# Board_ESP32_n_2Bluepill.net
KiCad netlist of a schematic drawn in EAGLE
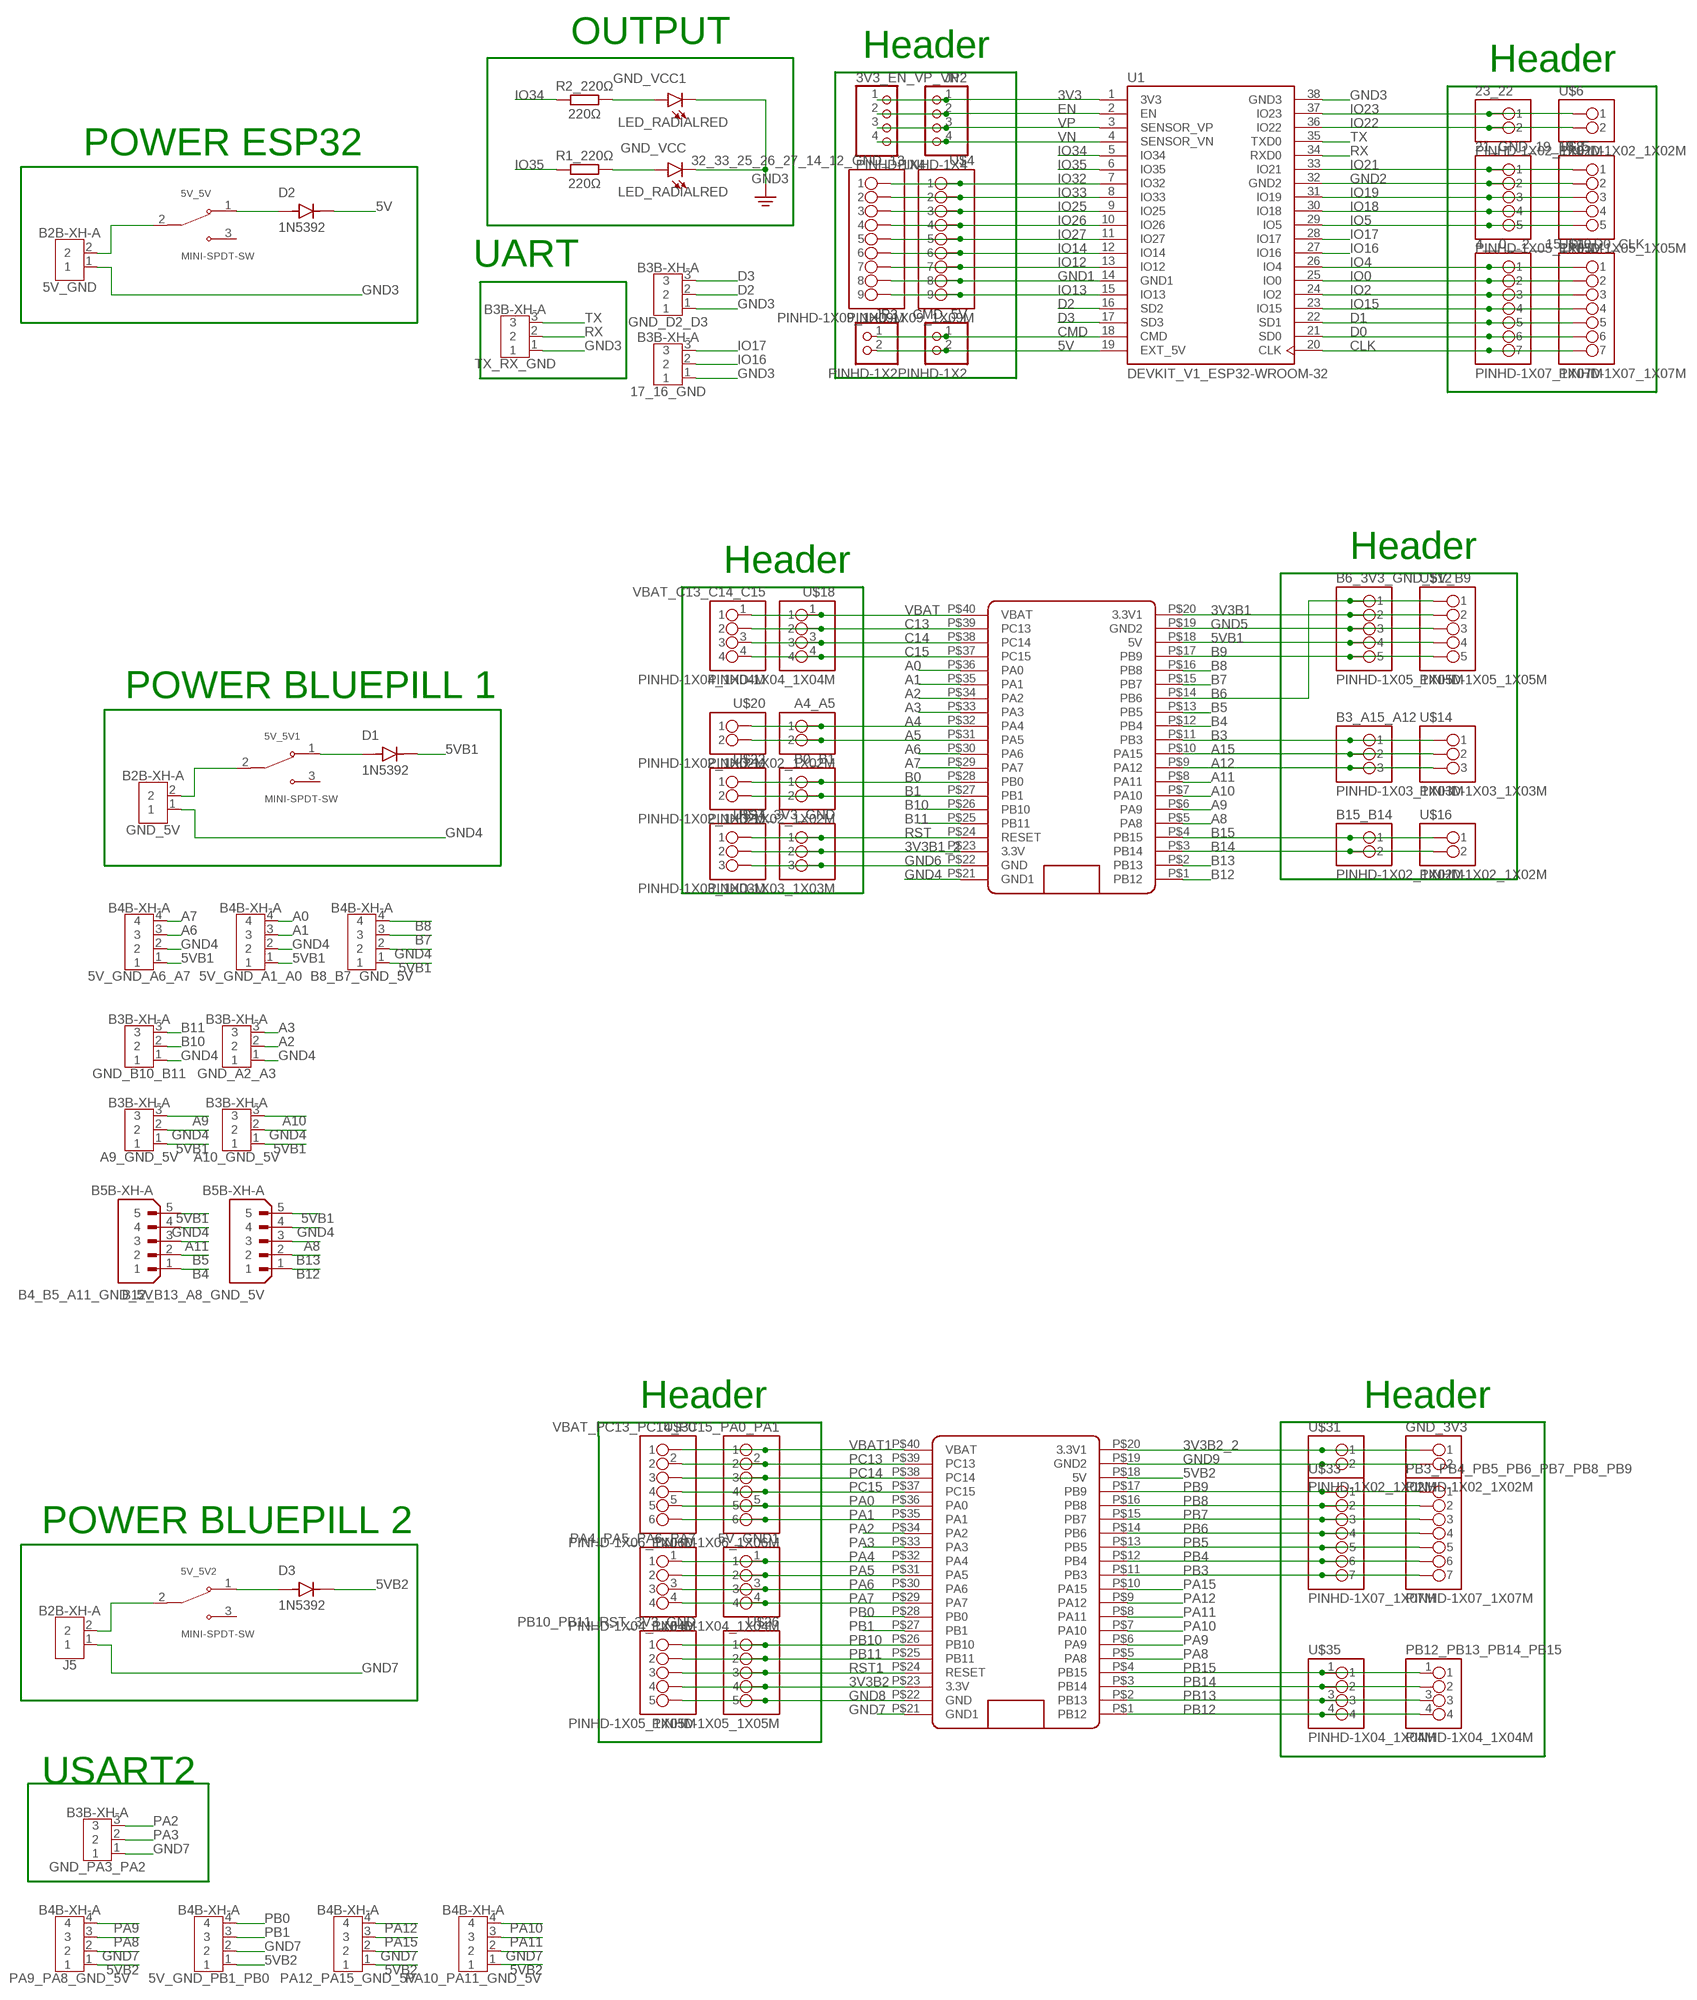
[diagram p0: schematic, sheet 1]

(export (version "E")
  (design (tool "Eeschema 10.0.6"))
  (components
    (comp (ref "3V3_EN_VP_VN")
      (value "PINHD-1X4")
      (footprint "eagle-import:1X04")
      (libsource (lib "eagle-import") (part "PINHD-1X4"))
    )
    (comp (ref "4__0__2__15_D1_D0_CLK")
      (value "PINHD-1X07_1X07M")
      (footprint "eagle-import:1X07")
      (libsource (lib "eagle-import") (part "PINHD-1X07_1X07M"))
    )
    (comp (ref "5V_5V")
      (value "MINI-SPDT-SW")
      (footprint "eagle-import:SW_MINI-SPDT-SW")
      (fields (field (name "MF") "Gravitech"))
      (libsource (lib "eagle-import") (part "MINI-SPDT-SW"))
    )
    (comp (ref "5V_5V1")
      (value "MINI-SPDT-SW")
      (footprint "eagle-import:SW_MINI-SPDT-SW")
      (fields (field (name "MF") "Gravitech"))
      (libsource (lib "eagle-import") (part "MINI-SPDT-SW"))
    )
    (comp (ref "5V_5V2")
      (value "MINI-SPDT-SW")
      (footprint "eagle-import:SW_MINI-SPDT-SW")
      (fields (field (name "MF") "Gravitech"))
      (libsource (lib "eagle-import") (part "MINI-SPDT-SW"))
    )
    (comp (ref "5V_GND")
      (value "B2B-XH-A")
      (footprint "eagle-import:B2B-XH-A")
      (fields (field (name "MANUFACTURER") "JST Sales America Inc."))
      (libsource (lib "eagle-import") (part "B2B-XH-A"))
    )
    (comp (ref "5V_GND1")
      (value "PINHD-1X04_1X04M")
      (footprint "eagle-import:1X04")
      (libsource (lib "eagle-import") (part "PINHD-1X04_1X04M"))
    )
    (comp (ref "5V_GND_A1_A0")
      (value "B4B-XH-A")
      (footprint "eagle-import:B4B-XH-A")
      (fields (field (name "MANUFACTURER") "JST Sales America Inc."))
      (libsource (lib "eagle-import") (part "B4B-XH-A"))
    )
    (comp (ref "5V_GND_A6_A7")
      (value "B4B-XH-A")
      (footprint "eagle-import:B4B-XH-A")
      (fields (field (name "MANUFACTURER") "JST Sales America Inc."))
      (libsource (lib "eagle-import") (part "B4B-XH-A"))
    )
    (comp (ref "5V_GND_PB1_PB0")
      (value "B4B-XH-A")
      (footprint "eagle-import:B4B-XH-A")
      (fields (field (name "MANUFACTURER") "JST Sales America Inc."))
      (libsource (lib "eagle-import") (part "B4B-XH-A"))
    )
    (comp (ref "17_16_GND")
      (value "B3B-XH-A")
      (footprint "eagle-import:B3B-XH-A")
      (fields (field (name "MANUFACTURER") "JST Sales America Inc."))
      (libsource (lib "eagle-import") (part "B3B-XH-A"))
    )
    (comp (ref "21_GND_19_18_5")
      (value "PINHD-1X05_1X05M")
      (footprint "eagle-import:1X05")
      (libsource (lib "eagle-import") (part "PINHD-1X05_1X05M"))
    )
    (comp (ref "23_22")
      (value "PINHD-1X02_1X02M")
      (footprint "eagle-import:1X02")
      (libsource (lib "eagle-import") (part "PINHD-1X02_1X02M"))
    )
    (comp (ref "32_33_25_26_27_14_12_GND_13")
      (value "PINHD-1X09_1X09M")
      (footprint "eagle-import:1X09")
      (libsource (lib "eagle-import") (part "PINHD-1X09_1X09M"))
    )
    (comp (ref "A4_A5")
      (value "PINHD-1X02_1X02M")
      (footprint "eagle-import:1X02")
      (libsource (lib "eagle-import") (part "PINHD-1X02_1X02M"))
    )
    (comp (ref "A9_GND_5V")
      (value "B3B-XH-A")
      (footprint "eagle-import:B3B-XH-A")
      (fields (field (name "MANUFACTURER") "JST Sales America Inc."))
      (libsource (lib "eagle-import") (part "B3B-XH-A"))
    )
    (comp (ref "A10_GND_5V")
      (value "B3B-XH-A")
      (footprint "eagle-import:B3B-XH-A")
      (fields (field (name "MANUFACTURER") "JST Sales America Inc."))
      (libsource (lib "eagle-import") (part "B3B-XH-A"))
    )
    (comp (ref "B0_B1")
      (value "PINHD-1X02_1X02M")
      (footprint "eagle-import:1X02")
      (libsource (lib "eagle-import") (part "PINHD-1X02_1X02M"))
    )
    (comp (ref "B3_A15_A12")
      (value "PINHD-1X03_1X03M")
      (footprint "eagle-import:1X03")
      (libsource (lib "eagle-import") (part "PINHD-1X03_1X03M"))
    )
    (comp (ref "B4_B5_A11_GND_5V")
      (value "B5B-XH-A")
      (footprint "eagle-import:JST_B5B-XH-A")
      (fields (field (name "MF") "JST Sales"))
      (libsource (lib "eagle-import") (part "B5B-XH-A"))
    )
    (comp (ref "B6_3V3_GND_5V_B9")
      (value "PINHD-1X05_1X05M")
      (footprint "eagle-import:1X05")
      (libsource (lib "eagle-import") (part "PINHD-1X05_1X05M"))
    )
    (comp (ref "B8_B7_GND_5V")
      (value "B4B-XH-A")
      (footprint "eagle-import:B4B-XH-A")
      (fields (field (name "MANUFACTURER") "JST Sales America Inc."))
      (libsource (lib "eagle-import") (part "B4B-XH-A"))
    )
    (comp (ref "B12_B13_A8_GND_5V")
      (value "B5B-XH-A")
      (footprint "eagle-import:JST_B5B-XH-A")
      (fields (field (name "MF") "JST Sales"))
      (libsource (lib "eagle-import") (part "B5B-XH-A"))
    )
    (comp (ref "B15_B14")
      (value "PINHD-1X02_1X02M")
      (footprint "eagle-import:1X02")
      (libsource (lib "eagle-import") (part "PINHD-1X02_1X02M"))
    )
    (comp (ref "CMD_5V")
      (value "PINHD-1X2")
      (footprint "eagle-import:1X02")
      (libsource (lib "eagle-import") (part "PINHD-1X2"))
    )
    (comp (ref "D1")
      (value "1N5392")
      (footprint "eagle-import:DIOAD1300W80L670D310")
      (fields (field (name "MF") "ON Semiconductor"))
      (libsource (lib "eagle-import") (part "1N5392"))
    )
    (comp (ref "D2")
      (value "1N5392")
      (footprint "eagle-import:DIOAD1300W80L670D310")
      (fields (field (name "MF") "ON Semiconductor"))
      (libsource (lib "eagle-import") (part "1N5392"))
    )
    (comp (ref "D3")
      (value "1N5392")
      (footprint "eagle-import:DIOAD1300W80L670D310")
      (fields (field (name "MF") "ON Semiconductor"))
      (libsource (lib "eagle-import") (part "1N5392"))
    )
    (comp (ref "GND_3V3")
      (value "PINHD-1X02_1X02M")
      (footprint "eagle-import:1X02")
      (libsource (lib "eagle-import") (part "PINHD-1X02_1X02M"))
    )
    (comp (ref "GND_5V")
      (value "B2B-XH-A")
      (footprint "eagle-import:B2B-XH-A")
      (fields (field (name "MANUFACTURER") "JST Sales America Inc."))
      (libsource (lib "eagle-import") (part "B2B-XH-A"))
    )
    (comp (ref "GND_A2_A3")
      (value "B3B-XH-A")
      (footprint "eagle-import:B3B-XH-A")
      (fields (field (name "MANUFACTURER") "JST Sales America Inc."))
      (libsource (lib "eagle-import") (part "B3B-XH-A"))
    )
    (comp (ref "GND_B10_B11")
      (value "B3B-XH-A")
      (footprint "eagle-import:B3B-XH-A")
      (fields (field (name "MANUFACTURER") "JST Sales America Inc."))
      (libsource (lib "eagle-import") (part "B3B-XH-A"))
    )
    (comp (ref "GND_D2_D3")
      (value "B3B-XH-A")
      (footprint "eagle-import:B3B-XH-A")
      (fields (field (name "MANUFACTURER") "JST Sales America Inc."))
      (libsource (lib "eagle-import") (part "B3B-XH-A"))
    )
    (comp (ref "GND_PA3_PA2")
      (value "B3B-XH-A")
      (footprint "eagle-import:B3B-XH-A")
      (fields (field (name "MANUFACTURER") "JST Sales America Inc."))
      (libsource (lib "eagle-import") (part "B3B-XH-A"))
    )
    (comp (ref "GND_VCC")
      (value "LED_RADIALRED")
      (footprint "eagle-import:LEDRD254W60D565H860B_R")
      (libsource (lib "eagle-import") (part "LED_RADIALRED"))
    )
    (comp (ref "GND_VCC1")
      (value "LED_RADIALRED")
      (footprint "eagle-import:LEDRD254W60D565H860B_R")
      (libsource (lib "eagle-import") (part "LED_RADIALRED"))
    )
    (comp (ref "J5")
      (value "B2B-XH-A")
      (footprint "eagle-import:B2B-XH-A")
      (fields (field (name "MANUFACTURER") "JST Sales America Inc."))
      (libsource (lib "eagle-import") (part "B2B-XH-A"))
    )
    (comp (ref "JP2")
      (value "PINHD-1X4")
      (footprint "eagle-import:1X04")
      (libsource (lib "eagle-import") (part "PINHD-1X4"))
    )
    (comp (ref "JP3")
      (value "PINHD-1X2")
      (footprint "eagle-import:1X02")
      (libsource (lib "eagle-import") (part "PINHD-1X2"))
    )
    (comp (ref "PA4_PA5_PA6_PA7")
      (value "PINHD-1X04_1X04M")
      (footprint "eagle-import:1X04")
      (libsource (lib "eagle-import") (part "PINHD-1X04_1X04M"))
    )
    (comp (ref "PA9_PA8_GND_5V")
      (value "B4B-XH-A")
      (footprint "eagle-import:B4B-XH-A")
      (fields (field (name "MANUFACTURER") "JST Sales America Inc."))
      (libsource (lib "eagle-import") (part "B4B-XH-A"))
    )
    (comp (ref "PA10_PA11_GND_5V")
      (value "B4B-XH-A")
      (footprint "eagle-import:B4B-XH-A")
      (fields (field (name "MANUFACTURER") "JST Sales America Inc."))
      (libsource (lib "eagle-import") (part "B4B-XH-A"))
    )
    (comp (ref "PA12_PA15_GND_5V")
      (value "B4B-XH-A")
      (footprint "eagle-import:B4B-XH-A")
      (fields (field (name "MANUFACTURER") "JST Sales America Inc."))
      (libsource (lib "eagle-import") (part "B4B-XH-A"))
    )
    (comp (ref "PB3_PB4_PB5_PB6_PB7_PB8_PB9")
      (value "PINHD-1X07_1X07M")
      (footprint "eagle-import:1X07")
      (libsource (lib "eagle-import") (part "PINHD-1X07_1X07M"))
    )
    (comp (ref "PB10_PB11_RST_3V3_GND")
      (value "PINHD-1X05_1X05M")
      (footprint "eagle-import:1X05")
      (libsource (lib "eagle-import") (part "PINHD-1X05_1X05M"))
    )
    (comp (ref "PB12_PB13_PB14_PB15")
      (value "PINHD-1X04_1X04M")
      (footprint "eagle-import:1X04")
      (libsource (lib "eagle-import") (part "PINHD-1X04_1X04M"))
    )
    (comp (ref "R1_220Ω")
      (value "220Ω")
      (footprint "eagle-import:RESAD1176W63L850D250B")
      (libsource (lib "eagle-import") (part "RAXIAL-11.7MM-PITCH_"))
    )
    (comp (ref "R2_220Ω")
      (value "220Ω")
      (footprint "eagle-import:RESAD1176W63L850D250B")
      (libsource (lib "eagle-import") (part "RAXIAL-11.7MM-PITCH_"))
    )
    (comp (ref "RST_3V3_GND")
      (value "PINHD-1X03_1X03M")
      (footprint "eagle-import:1X03")
      (libsource (lib "eagle-import") (part "PINHD-1X03_1X03M"))
    )
    (comp (ref "TX_RX_GND")
      (value "B3B-XH-A")
      (footprint "eagle-import:B3B-XH-A")
      (fields (field (name "MANUFACTURER") "JST Sales America Inc."))
      (libsource (lib "eagle-import") (part "B3B-XH-A"))
    )
    (comp (ref "U$1")
      (value "BLUE_PILL")
      (footprint "eagle-import:BLUE_PILL")
      (libsource (lib "eagle-import") (part "BLUE_PILL"))
    )
    (comp (ref "U$2")
      (value "BLUE_PILL")
      (footprint "eagle-import:BLUE_PILL")
      (libsource (lib "eagle-import") (part "BLUE_PILL"))
    )
    (comp (ref "U$4")
      (value "PINHD-1X09_1X09M")
      (footprint "eagle-import:1X09")
      (libsource (lib "eagle-import") (part "PINHD-1X09_1X09M"))
    )
    (comp (ref "U$6")
      (value "PINHD-1X02_1X02M")
      (footprint "eagle-import:1X02")
      (libsource (lib "eagle-import") (part "PINHD-1X02_1X02M"))
    )
    (comp (ref "U$8")
      (value "PINHD-1X05_1X05M")
      (footprint "eagle-import:1X05")
      (libsource (lib "eagle-import") (part "PINHD-1X05_1X05M"))
    )
    (comp (ref "U$10")
      (value "PINHD-1X07_1X07M")
      (footprint "eagle-import:1X07")
      (libsource (lib "eagle-import") (part "PINHD-1X07_1X07M"))
    )
    (comp (ref "U$12")
      (value "PINHD-1X05_1X05M")
      (footprint "eagle-import:1X05")
      (libsource (lib "eagle-import") (part "PINHD-1X05_1X05M"))
    )
    (comp (ref "U$14")
      (value "PINHD-1X03_1X03M")
      (footprint "eagle-import:1X03")
      (libsource (lib "eagle-import") (part "PINHD-1X03_1X03M"))
    )
    (comp (ref "U$16")
      (value "PINHD-1X02_1X02M")
      (footprint "eagle-import:1X02")
      (libsource (lib "eagle-import") (part "PINHD-1X02_1X02M"))
    )
    (comp (ref "U$18")
      (value "PINHD-1X04_1X04M")
      (footprint "eagle-import:1X04")
      (libsource (lib "eagle-import") (part "PINHD-1X04_1X04M"))
    )
    (comp (ref "U$20")
      (value "PINHD-1X02_1X02M")
      (footprint "eagle-import:1X02")
      (libsource (lib "eagle-import") (part "PINHD-1X02_1X02M"))
    )
    (comp (ref "U$22")
      (value "PINHD-1X02_1X02M")
      (footprint "eagle-import:1X02")
      (libsource (lib "eagle-import") (part "PINHD-1X02_1X02M"))
    )
    (comp (ref "U$24")
      (value "PINHD-1X03_1X03M")
      (footprint "eagle-import:1X03")
      (libsource (lib "eagle-import") (part "PINHD-1X03_1X03M"))
    )
    (comp (ref "U$26")
      (value "PINHD-1X05_1X05M")
      (footprint "eagle-import:1X05")
      (libsource (lib "eagle-import") (part "PINHD-1X05_1X05M"))
    )
    (comp (ref "U$30")
      (value "PINHD-1X06_1X06M")
      (footprint "eagle-import:1X06")
      (libsource (lib "eagle-import") (part "PINHD-1X06_1X06M"))
    )
    (comp (ref "U$31")
      (value "PINHD-1X02_1X02M")
      (footprint "eagle-import:1X02")
      (libsource (lib "eagle-import") (part "PINHD-1X02_1X02M"))
    )
    (comp (ref "U$33")
      (value "PINHD-1X07_1X07M")
      (footprint "eagle-import:1X07")
      (libsource (lib "eagle-import") (part "PINHD-1X07_1X07M"))
    )
    (comp (ref "U$35")
      (value "PINHD-1X04_1X04M")
      (footprint "eagle-import:1X04")
      (libsource (lib "eagle-import") (part "PINHD-1X04_1X04M"))
    )
    (comp (ref "U1")
      (value "DEVKIT_V1_ESP32-WROOM-32")
      (footprint "eagle-import:MODULE_DEVKIT_V1_ESP32-WROOM-32")
      (fields (field (name "MF") "Espressif Systems") (field (name "MP") "DEVKIT V1 ESP32-WROOM-32"))
      (libsource (lib "eagle-import") (part "DEVKIT_V1_ESP32-WROOM-32"))
    )
    (comp (ref "VBAT_C13_C14_C15")
      (value "PINHD-1X04_1X04M")
      (footprint "eagle-import:1X04")
      (libsource (lib "eagle-import") (part "PINHD-1X04_1X04M"))
    )
    (comp (ref "VBAT_PC13_PC14_PC15_PA0_PA1")
      (value "PINHD-1X06_1X06M")
      (footprint "eagle-import:1X06")
      (libsource (lib "eagle-import") (part "PINHD-1X06_1X06M"))
    )
  )
  (nets
    (net (code "1") (name "/3V3") (class "Default")
      (node (ref "3V3_EN_VP_VN") (pin "1") (pinfunction "1_1") (pintype "passive"))
      (node (ref "JP2") (pin "1") (pinfunction "1_1") (pintype "passive"))
      (node (ref "U1") (pin "1") (pinfunction "3V3_1") (pintype "power_in"))
    )
    (net (code "2") (name "/3V3B1") (class "Default")
      (node (ref "B6_3V3_GND_5V_B9") (pin "2") (pinfunction "2_2") (pintype "bidirectional"))
      (node (ref "U$1") (pin "P$20") (pinfunction "3.3V1_P$20") (pintype "bidirectional"))
      (node (ref "U$12") (pin "2") (pinfunction "2_2") (pintype "bidirectional"))
    )
    (net (code "3") (name "/3V3B1_2") (class "Default")
      (node (ref "RST_3V3_GND") (pin "2") (pinfunction "2_2") (pintype "bidirectional"))
      (node (ref "U$1") (pin "P$23") (pinfunction "3.3V_P$23") (pintype "bidirectional"))
      (node (ref "U$24") (pin "2") (pinfunction "2_2") (pintype "bidirectional"))
    )
    (net (code "4") (name "/3V3B2") (class "Default")
      (node (ref "PB10_PB11_RST_3V3_GND") (pin "4") (pinfunction "4_4") (pintype "bidirectional"))
      (node (ref "U$2") (pin "P$23") (pinfunction "3.3V_P$23") (pintype "bidirectional"))
      (node (ref "U$26") (pin "4") (pinfunction "4_4") (pintype "bidirectional"))
    )
    (net (code "5") (name "/3V3B2_2") (class "Default")
      (node (ref "GND_3V3") (pin "1") (pinfunction "1_1") (pintype "bidirectional"))
      (node (ref "U$2") (pin "P$20") (pinfunction "3.3V1_P$20") (pintype "bidirectional"))
      (node (ref "U$31") (pin "1") (pinfunction "1_1") (pintype "bidirectional"))
    )
    (net (code "6") (name "/5V") (class "Default")
      (node (ref "CMD_5V") (pin "2") (pinfunction "2_2") (pintype "passive"))
      (node (ref "D2") (pin "C") (pinfunction "K_C") (pintype "passive"))
      (node (ref "JP3") (pin "2") (pinfunction "2_2") (pintype "passive"))
      (node (ref "U1") (pin "19") (pinfunction "EXT_5V_19") (pintype "power_in"))
    )
    (net (code "7") (name "/5VB1") (class "Default")
      (node (ref "5V_GND_A1_A0") (pin "1") (pinfunction "1_1") (pintype "bidirectional"))
      (node (ref "5V_GND_A6_A7") (pin "1") (pinfunction "1_1") (pintype "bidirectional"))
      (node (ref "A10_GND_5V") (pin "1") (pinfunction "1_1") (pintype "bidirectional"))
      (node (ref "A9_GND_5V") (pin "1") (pinfunction "1_1") (pintype "bidirectional"))
      (node (ref "B12_B13_A8_GND_5V") (pin "5") (pinfunction "5_5") (pintype "passive"))
      (node (ref "B4_B5_A11_GND_5V") (pin "5") (pinfunction "5_5") (pintype "passive"))
      (node (ref "B6_3V3_GND_5V_B9") (pin "4") (pinfunction "4_4") (pintype "bidirectional"))
      (node (ref "B8_B7_GND_5V") (pin "1") (pinfunction "1_1") (pintype "bidirectional"))
      (node (ref "D1") (pin "C") (pinfunction "K_C") (pintype "passive"))
      (node (ref "U$1") (pin "P$18") (pinfunction "5V_P$18") (pintype "bidirectional"))
      (node (ref "U$12") (pin "4") (pinfunction "4_4") (pintype "bidirectional"))
    )
    (net (code "8") (name "/5VB2") (class "Default")
      (node (ref "5V_GND_PB1_PB0") (pin "1") (pinfunction "1_1") (pintype "bidirectional"))
      (node (ref "D3") (pin "C") (pinfunction "K_C") (pintype "passive"))
      (node (ref "PA10_PA11_GND_5V") (pin "1") (pinfunction "1_1") (pintype "bidirectional"))
      (node (ref "PA12_PA15_GND_5V") (pin "1") (pinfunction "1_1") (pintype "bidirectional"))
      (node (ref "PA9_PA8_GND_5V") (pin "1") (pinfunction "1_1") (pintype "bidirectional"))
      (node (ref "U$2") (pin "P$18") (pinfunction "5V_P$18") (pintype "bidirectional"))
    )
    (net (code "9") (name "/A0") (class "Default")
      (node (ref "5V_GND_A1_A0") (pin "4") (pinfunction "4_4") (pintype "bidirectional"))
      (node (ref "U$1") (pin "P$36") (pinfunction "PA0_P$36") (pintype "bidirectional"))
    )
    (net (code "10") (name "/A1") (class "Default")
      (node (ref "5V_GND_A1_A0") (pin "3") (pinfunction "3_3") (pintype "bidirectional"))
      (node (ref "U$1") (pin "P$35") (pinfunction "PA1_P$35") (pintype "bidirectional"))
    )
    (net (code "11") (name "/A2") (class "Default")
      (node (ref "GND_A2_A3") (pin "2") (pinfunction "2_2") (pintype "bidirectional"))
      (node (ref "U$1") (pin "P$34") (pinfunction "PA2_P$34") (pintype "bidirectional"))
    )
    (net (code "12") (name "/A3") (class "Default")
      (node (ref "GND_A2_A3") (pin "3") (pinfunction "3_3") (pintype "bidirectional"))
      (node (ref "U$1") (pin "P$33") (pinfunction "PA3_P$33") (pintype "bidirectional"))
    )
    (net (code "13") (name "/A4") (class "Default")
      (node (ref "A4_A5") (pin "1") (pinfunction "1_1") (pintype "bidirectional"))
      (node (ref "U$1") (pin "P$32") (pinfunction "PA4_P$32") (pintype "bidirectional"))
      (node (ref "U$20") (pin "1") (pinfunction "1_1") (pintype "bidirectional"))
    )
    (net (code "14") (name "/A5") (class "Default")
      (node (ref "A4_A5") (pin "2") (pinfunction "2_2") (pintype "bidirectional"))
      (node (ref "U$1") (pin "P$31") (pinfunction "PA5_P$31") (pintype "bidirectional"))
      (node (ref "U$20") (pin "2") (pinfunction "2_2") (pintype "bidirectional"))
    )
    (net (code "15") (name "/A6") (class "Default")
      (node (ref "5V_GND_A6_A7") (pin "3") (pinfunction "3_3") (pintype "bidirectional"))
      (node (ref "U$1") (pin "P$30") (pinfunction "PA6_P$30") (pintype "bidirectional"))
    )
    (net (code "16") (name "/A7") (class "Default")
      (node (ref "5V_GND_A6_A7") (pin "4") (pinfunction "4_4") (pintype "bidirectional"))
      (node (ref "U$1") (pin "P$29") (pinfunction "PA7_P$29") (pintype "bidirectional"))
    )
    (net (code "17") (name "/A8") (class "Default")
      (node (ref "B12_B13_A8_GND_5V") (pin "3") (pinfunction "3_3") (pintype "passive"))
      (node (ref "U$1") (pin "P$5") (pinfunction "PA8_P$5") (pintype "bidirectional"))
    )
    (net (code "18") (name "/A9") (class "Default")
      (node (ref "A9_GND_5V") (pin "3") (pinfunction "3_3") (pintype "bidirectional"))
      (node (ref "U$1") (pin "P$6") (pinfunction "PA9_P$6") (pintype "bidirectional"))
    )
    (net (code "19") (name "/A10") (class "Default")
      (node (ref "A10_GND_5V") (pin "3") (pinfunction "3_3") (pintype "bidirectional"))
      (node (ref "U$1") (pin "P$7") (pinfunction "PA10_P$7") (pintype "bidirectional"))
    )
    (net (code "20") (name "/A11") (class "Default")
      (node (ref "B4_B5_A11_GND_5V") (pin "3") (pinfunction "3_3") (pintype "passive"))
      (node (ref "U$1") (pin "P$8") (pinfunction "PA11_P$8") (pintype "bidirectional"))
    )
    (net (code "21") (name "/A12") (class "Default")
      (node (ref "B3_A15_A12") (pin "3") (pinfunction "3_3") (pintype "bidirectional"))
      (node (ref "U$1") (pin "P$9") (pinfunction "PA12_P$9") (pintype "bidirectional"))
      (node (ref "U$14") (pin "3") (pinfunction "3_3") (pintype "bidirectional"))
    )
    (net (code "22") (name "/A15") (class "Default")
      (node (ref "B3_A15_A12") (pin "2") (pinfunction "2_2") (pintype "bidirectional"))
      (node (ref "U$1") (pin "P$10") (pinfunction "PA15_P$10") (pintype "bidirectional"))
      (node (ref "U$14") (pin "2") (pinfunction "2_2") (pintype "bidirectional"))
    )
    (net (code "23") (name "/B0") (class "Default")
      (node (ref "B0_B1") (pin "1") (pinfunction "1_1") (pintype "bidirectional"))
      (node (ref "U$1") (pin "P$28") (pinfunction "PB0_P$28") (pintype "bidirectional"))
      (node (ref "U$22") (pin "1") (pinfunction "1_1") (pintype "bidirectional"))
    )
    (net (code "24") (name "/B1") (class "Default")
      (node (ref "B0_B1") (pin "2") (pinfunction "2_2") (pintype "bidirectional"))
      (node (ref "U$1") (pin "P$27") (pinfunction "PB1_P$27") (pintype "bidirectional"))
      (node (ref "U$22") (pin "2") (pinfunction "2_2") (pintype "bidirectional"))
    )
    (net (code "25") (name "/B3") (class "Default")
      (node (ref "B3_A15_A12") (pin "1") (pinfunction "1_1") (pintype "bidirectional"))
      (node (ref "U$1") (pin "P$11") (pinfunction "PB3_P$11") (pintype "bidirectional"))
      (node (ref "U$14") (pin "1") (pinfunction "1_1") (pintype "bidirectional"))
    )
    (net (code "26") (name "/B4") (class "Default")
      (node (ref "B4_B5_A11_GND_5V") (pin "1") (pinfunction "1_1") (pintype "passive"))
      (node (ref "U$1") (pin "P$12") (pinfunction "PB4_P$12") (pintype "bidirectional"))
    )
    (net (code "27") (name "/B5") (class "Default")
      (node (ref "B4_B5_A11_GND_5V") (pin "2") (pinfunction "2_2") (pintype "passive"))
      (node (ref "U$1") (pin "P$13") (pinfunction "PB5_P$13") (pintype "bidirectional"))
    )
    (net (code "28") (name "/B6") (class "Default")
      (node (ref "B6_3V3_GND_5V_B9") (pin "1") (pinfunction "1_1") (pintype "bidirectional"))
      (node (ref "U$1") (pin "P$14") (pinfunction "PB6_P$14") (pintype "bidirectional"))
      (node (ref "U$12") (pin "1") (pinfunction "1_1") (pintype "bidirectional"))
    )
    (net (code "29") (name "/B7") (class "Default")
      (node (ref "B8_B7_GND_5V") (pin "3") (pinfunction "3_3") (pintype "bidirectional"))
      (node (ref "U$1") (pin "P$15") (pinfunction "PB7_P$15") (pintype "bidirectional"))
    )
    (net (code "30") (name "/B8") (class "Default")
      (node (ref "B8_B7_GND_5V") (pin "4") (pinfunction "4_4") (pintype "bidirectional"))
      (node (ref "U$1") (pin "P$16") (pinfunction "PB8_P$16") (pintype "bidirectional"))
    )
    (net (code "31") (name "/B9") (class "Default")
      (node (ref "B6_3V3_GND_5V_B9") (pin "5") (pinfunction "5_5") (pintype "bidirectional"))
      (node (ref "U$1") (pin "P$17") (pinfunction "PB9_P$17") (pintype "bidirectional"))
      (node (ref "U$12") (pin "5") (pinfunction "5_5") (pintype "bidirectional"))
    )
    (net (code "32") (name "/B10") (class "Default")
      (node (ref "GND_B10_B11") (pin "2") (pinfunction "2_2") (pintype "bidirectional"))
      (node (ref "U$1") (pin "P$26") (pinfunction "PB10_P$26") (pintype "bidirectional"))
    )
    (net (code "33") (name "/B11") (class "Default")
      (node (ref "GND_B10_B11") (pin "3") (pinfunction "3_3") (pintype "bidirectional"))
      (node (ref "U$1") (pin "P$25") (pinfunction "PB11_P$25") (pintype "bidirectional"))
    )
    (net (code "34") (name "/B12") (class "Default")
      (node (ref "B12_B13_A8_GND_5V") (pin "1") (pinfunction "1_1") (pintype "passive"))
      (node (ref "U$1") (pin "P$1") (pinfunction "PB12_P$1") (pintype "bidirectional"))
    )
    (net (code "35") (name "/B13") (class "Default")
      (node (ref "B12_B13_A8_GND_5V") (pin "2") (pinfunction "2_2") (pintype "passive"))
      (node (ref "U$1") (pin "P$2") (pinfunction "PB13_P$2") (pintype "bidirectional"))
    )
    (net (code "36") (name "/B14") (class "Default")
      (node (ref "B15_B14") (pin "2") (pinfunction "2_2") (pintype "bidirectional"))
      (node (ref "U$1") (pin "P$3") (pinfunction "PB14_P$3") (pintype "bidirectional"))
      (node (ref "U$16") (pin "2") (pinfunction "2_2") (pintype "bidirectional"))
    )
    (net (code "37") (name "/B15") (class "Default")
      (node (ref "B15_B14") (pin "1") (pinfunction "1_1") (pintype "bidirectional"))
      (node (ref "U$1") (pin "P$4") (pinfunction "PB15_P$4") (pintype "bidirectional"))
      (node (ref "U$16") (pin "1") (pinfunction "1_1") (pintype "bidirectional"))
    )
    (net (code "38") (name "/C13") (class "Default")
      (node (ref "U$1") (pin "P$39") (pinfunction "PC13_P$39") (pintype "bidirectional"))
      (node (ref "U$18") (pin "2") (pinfunction "2_2") (pintype "bidirectional"))
      (node (ref "VBAT_C13_C14_C15") (pin "2") (pinfunction "2_2") (pintype "bidirectional"))
    )
    (net (code "39") (name "/C14") (class "Default")
      (node (ref "U$1") (pin "P$38") (pinfunction "PC14_P$38") (pintype "bidirectional"))
      (node (ref "U$18") (pin "3") (pinfunction "3_3") (pintype "bidirectional"))
      (node (ref "VBAT_C13_C14_C15") (pin "3") (pinfunction "3_3") (pintype "bidirectional"))
    )
    (net (code "40") (name "/C15") (class "Default")
      (node (ref "U$1") (pin "P$37") (pinfunction "PC15_P$37") (pintype "bidirectional"))
      (node (ref "U$18") (pin "4") (pinfunction "4_4") (pintype "bidirectional"))
      (node (ref "VBAT_C13_C14_C15") (pin "4") (pinfunction "4_4") (pintype "bidirectional"))
    )
    (net (code "41") (name "/CLK") (class "Default")
      (node (ref "4__0__2__15_D1_D0_CLK") (pin "7") (pinfunction "7_7") (pintype "bidirectional"))
      (node (ref "U$10") (pin "7") (pinfunction "7_7") (pintype "bidirectional"))
      (node (ref "U1") (pin "20") (pinfunction "CLK_20") (pintype "input"))
    )
    (net (code "42") (name "/CMD") (class "Default")
      (node (ref "CMD_5V") (pin "1") (pinfunction "1_1") (pintype "passive"))
      (node (ref "JP3") (pin "1") (pinfunction "1_1") (pintype "passive"))
      (node (ref "U1") (pin "18") (pinfunction "CMD_18") (pintype "bidirectional"))
    )
    (net (code "43") (name "/D0") (class "Default")
      (node (ref "4__0__2__15_D1_D0_CLK") (pin "6") (pinfunction "6_6") (pintype "bidirectional"))
      (node (ref "U$10") (pin "6") (pinfunction "6_6") (pintype "bidirectional"))
      (node (ref "U1") (pin "21") (pinfunction "SD0_21") (pintype "bidirectional"))
    )
    (net (code "44") (name "/D1") (class "Default")
      (node (ref "4__0__2__15_D1_D0_CLK") (pin "5") (pinfunction "5_5") (pintype "bidirectional"))
      (node (ref "U$10") (pin "5") (pinfunction "5_5") (pintype "bidirectional"))
      (node (ref "U1") (pin "22") (pinfunction "SD1_22") (pintype "bidirectional"))
    )
    (net (code "45") (name "/D2") (class "Default")
      (node (ref "GND_D2_D3") (pin "2") (pinfunction "2_2") (pintype "bidirectional"))
      (node (ref "U1") (pin "16") (pinfunction "SD2_16") (pintype "bidirectional"))
    )
    (net (code "46") (name "/D3") (class "Default")
      (node (ref "GND_D2_D3") (pin "3") (pinfunction "3_3") (pintype "bidirectional"))
      (node (ref "U1") (pin "17") (pinfunction "SD3_17") (pintype "bidirectional"))
    )
    (net (code "47") (name "/EN") (class "Default")
      (node (ref "3V3_EN_VP_VN") (pin "2") (pinfunction "2_2") (pintype "passive"))
      (node (ref "JP2") (pin "2") (pinfunction "2_2") (pintype "passive"))
      (node (ref "U1") (pin "2") (pinfunction "EN_2") (pintype "input"))
    )
    (net (code "48") (name "/GND1") (class "Default")
      (node (ref "32_33_25_26_27_14_12_GND_13") (pin "8") (pinfunction "8_8") (pintype "bidirectional"))
      (node (ref "U$4") (pin "8") (pinfunction "8_8") (pintype "bidirectional"))
      (node (ref "U1") (pin "14") (pinfunction "GND1_14") (pintype "power_in"))
    )
    (net (code "49") (name "/GND2") (class "Default")
      (node (ref "21_GND_19_18_5") (pin "2") (pinfunction "2_2") (pintype "bidirectional"))
      (node (ref "U$8") (pin "2") (pinfunction "2_2") (pintype "bidirectional"))
      (node (ref "U1") (pin "32") (pinfunction "GND2_32") (pintype "power_in"))
    )
    (net (code "50") (name "/GND4") (class "Default")
      (node (ref "5V_GND_A1_A0") (pin "2") (pinfunction "2_2") (pintype "bidirectional"))
      (node (ref "5V_GND_A6_A7") (pin "2") (pinfunction "2_2") (pintype "bidirectional"))
      (node (ref "A10_GND_5V") (pin "2") (pinfunction "2_2") (pintype "bidirectional"))
      (node (ref "A9_GND_5V") (pin "2") (pinfunction "2_2") (pintype "bidirectional"))
      (node (ref "B12_B13_A8_GND_5V") (pin "4") (pinfunction "4_4") (pintype "passive"))
      (node (ref "B4_B5_A11_GND_5V") (pin "4") (pinfunction "4_4") (pintype "passive"))
      (node (ref "B8_B7_GND_5V") (pin "2") (pinfunction "2_2") (pintype "bidirectional"))
      (node (ref "GND_5V") (pin "1") (pinfunction "1_1") (pintype "bidirectional"))
      (node (ref "GND_A2_A3") (pin "1") (pinfunction "1_1") (pintype "bidirectional"))
      (node (ref "GND_B10_B11") (pin "1") (pinfunction "1_1") (pintype "bidirectional"))
      (node (ref "U$1") (pin "P$21") (pinfunction "GND1_P$21") (pintype "power_in"))
    )
    (net (code "51") (name "/GND5") (class "Default")
      (node (ref "B6_3V3_GND_5V_B9") (pin "3") (pinfunction "3_3") (pintype "bidirectional"))
      (node (ref "U$1") (pin "P$19") (pinfunction "GND2_P$19") (pintype "bidirectional"))
      (node (ref "U$12") (pin "3") (pinfunction "3_3") (pintype "bidirectional"))
    )
    (net (code "52") (name "/GND6") (class "Default")
      (node (ref "RST_3V3_GND") (pin "3") (pinfunction "3_3") (pintype "bidirectional"))
      (node (ref "U$1") (pin "P$22") (pinfunction "GND_P$22") (pintype "bidirectional"))
      (node (ref "U$24") (pin "3") (pinfunction "3_3") (pintype "bidirectional"))
    )
    (net (code "53") (name "/GND7") (class "Default")
      (node (ref "5V_GND_PB1_PB0") (pin "2") (pinfunction "2_2") (pintype "bidirectional"))
      (node (ref "GND_PA3_PA2") (pin "1") (pinfunction "1_1") (pintype "bidirectional"))
      (node (ref "J5") (pin "1") (pinfunction "1_1") (pintype "bidirectional"))
      (node (ref "PA10_PA11_GND_5V") (pin "2") (pinfunction "2_2") (pintype "bidirectional"))
      (node (ref "PA12_PA15_GND_5V") (pin "2") (pinfunction "2_2") (pintype "bidirectional"))
      (node (ref "PA9_PA8_GND_5V") (pin "2") (pinfunction "2_2") (pintype "bidirectional"))
      (node (ref "U$2") (pin "P$21") (pinfunction "GND1_P$21") (pintype "power_in"))
    )
    (net (code "54") (name "/GND8") (class "Default")
      (node (ref "PB10_PB11_RST_3V3_GND") (pin "5") (pinfunction "5_5") (pintype "bidirectional"))
      (node (ref "U$2") (pin "P$22") (pinfunction "GND_P$22") (pintype "bidirectional"))
      (node (ref "U$26") (pin "5") (pinfunction "5_5") (pintype "bidirectional"))
    )
    (net (code "55") (name "/GND9") (class "Default")
      (node (ref "GND_3V3") (pin "2") (pinfunction "2_2") (pintype "bidirectional"))
      (node (ref "U$2") (pin "P$19") (pinfunction "GND2_P$19") (pintype "bidirectional"))
      (node (ref "U$31") (pin "2") (pinfunction "2_2") (pintype "bidirectional"))
    )
    (net (code "56") (name "/IO0") (class "Default")
      (node (ref "4__0__2__15_D1_D0_CLK") (pin "2") (pinfunction "2_2") (pintype "bidirectional"))
      (node (ref "U$10") (pin "2") (pinfunction "2_2") (pintype "bidirectional"))
      (node (ref "U1") (pin "25") (pinfunction "IO0_25") (pintype "bidirectional"))
    )
    (net (code "57") (name "/IO2") (class "Default")
      (node (ref "4__0__2__15_D1_D0_CLK") (pin "3") (pinfunction "3_3") (pintype "bidirectional"))
      (node (ref "U$10") (pin "3") (pinfunction "3_3") (pintype "bidirectional"))
      (node (ref "U1") (pin "24") (pinfunction "IO2_24") (pintype "bidirectional"))
    )
    (net (code "58") (name "/IO4") (class "Default")
      (node (ref "4__0__2__15_D1_D0_CLK") (pin "1") (pinfunction "1_1") (pintype "bidirectional"))
      (node (ref "U$10") (pin "1") (pinfunction "1_1") (pintype "bidirectional"))
      (node (ref "U1") (pin "26") (pinfunction "IO4_26") (pintype "bidirectional"))
    )
    (net (code "59") (name "/IO5") (class "Default")
      (node (ref "21_GND_19_18_5") (pin "5") (pinfunction "5_5") (pintype "bidirectional"))
      (node (ref "U$8") (pin "5") (pinfunction "5_5") (pintype "bidirectional"))
      (node (ref "U1") (pin "29") (pinfunction "IO5_29") (pintype "bidirectional"))
    )
    (net (code "60") (name "/IO12") (class "Default")
      (node (ref "32_33_25_26_27_14_12_GND_13") (pin "7") (pinfunction "7_7") (pintype "bidirectional"))
      (node (ref "U$4") (pin "7") (pinfunction "7_7") (pintype "bidirectional"))
      (node (ref "U1") (pin "13") (pinfunction "IO12_13") (pintype "bidirectional"))
    )
    (net (code "61") (name "/IO13") (class "Default")
      (node (ref "32_33_25_26_27_14_12_GND_13") (pin "9") (pinfunction "9_9") (pintype "bidirectional"))
      (node (ref "U$4") (pin "9") (pinfunction "9_9") (pintype "bidirectional"))
      (node (ref "U1") (pin "15") (pinfunction "IO13_15") (pintype "bidirectional"))
    )
    (net (code "62") (name "/IO14") (class "Default")
      (node (ref "32_33_25_26_27_14_12_GND_13") (pin "6") (pinfunction "6_6") (pintype "bidirectional"))
      (node (ref "U$4") (pin "6") (pinfunction "6_6") (pintype "bidirectional"))
      (node (ref "U1") (pin "12") (pinfunction "IO14_12") (pintype "bidirectional"))
    )
    (net (code "63") (name "/IO15") (class "Default")
      (node (ref "4__0__2__15_D1_D0_CLK") (pin "4") (pinfunction "4_4") (pintype "bidirectional"))
      (node (ref "U$10") (pin "4") (pinfunction "4_4") (pintype "bidirectional"))
      (node (ref "U1") (pin "23") (pinfunction "IO15_23") (pintype "bidirectional"))
    )
    (net (code "64") (name "/IO16") (class "Default")
      (node (ref "17_16_GND") (pin "2") (pinfunction "2_2") (pintype "bidirectional"))
      (node (ref "U1") (pin "27") (pinfunction "IO16_27") (pintype "bidirectional"))
    )
    (net (code "65") (name "/IO17") (class "Default")
      (node (ref "17_16_GND") (pin "3") (pinfunction "3_3") (pintype "bidirectional"))
      (node (ref "U1") (pin "28") (pinfunction "IO17_28") (pintype "bidirectional"))
    )
    (net (code "66") (name "/IO18") (class "Default")
      (node (ref "21_GND_19_18_5") (pin "4") (pinfunction "4_4") (pintype "bidirectional"))
      (node (ref "U$8") (pin "4") (pinfunction "4_4") (pintype "bidirectional"))
      (node (ref "U1") (pin "30") (pinfunction "IO18_30") (pintype "bidirectional"))
    )
    (net (code "67") (name "/IO19") (class "Default")
      (node (ref "21_GND_19_18_5") (pin "3") (pinfunction "3_3") (pintype "bidirectional"))
      (node (ref "U$8") (pin "3") (pinfunction "3_3") (pintype "bidirectional"))
      (node (ref "U1") (pin "31") (pinfunction "IO19_31") (pintype "bidirectional"))
    )
    (net (code "68") (name "/IO21") (class "Default")
      (node (ref "21_GND_19_18_5") (pin "1") (pinfunction "1_1") (pintype "bidirectional"))
      (node (ref "U$8") (pin "1") (pinfunction "1_1") (pintype "bidirectional"))
      (node (ref "U1") (pin "33") (pinfunction "IO21_33") (pintype "bidirectional"))
    )
    (net (code "69") (name "/IO22") (class "Default")
      (node (ref "23_22") (pin "2") (pinfunction "2_2") (pintype "bidirectional"))
      (node (ref "U$6") (pin "2") (pinfunction "2_2") (pintype "bidirectional"))
      (node (ref "U1") (pin "36") (pinfunction "IO22_36") (pintype "bidirectional"))
    )
    (net (code "70") (name "/IO23") (class "Default")
      (node (ref "23_22") (pin "1") (pinfunction "1_1") (pintype "bidirectional"))
      (node (ref "U$6") (pin "1") (pinfunction "1_1") (pintype "bidirectional"))
      (node (ref "U1") (pin "37") (pinfunction "IO23_37") (pintype "bidirectional"))
    )
    (net (code "71") (name "/IO25") (class "Default")
      (node (ref "32_33_25_26_27_14_12_GND_13") (pin "3") (pinfunction "3_3") (pintype "bidirectional"))
      (node (ref "U$4") (pin "3") (pinfunction "3_3") (pintype "bidirectional"))
      (node (ref "U1") (pin "9") (pinfunction "IO25_9") (pintype "bidirectional"))
    )
    (net (code "72") (name "/IO26") (class "Default")
      (node (ref "32_33_25_26_27_14_12_GND_13") (pin "4") (pinfunction "4_4") (pintype "bidirectional"))
      (node (ref "U$4") (pin "4") (pinfunction "4_4") (pintype "bidirectional"))
      (node (ref "U1") (pin "10") (pinfunction "IO26_10") (pintype "bidirectional"))
    )
    (net (code "73") (name "/IO27") (class "Default")
      (node (ref "32_33_25_26_27_14_12_GND_13") (pin "5") (pinfunction "5_5") (pintype "bidirectional"))
      (node (ref "U$4") (pin "5") (pinfunction "5_5") (pintype "bidirectional"))
      (node (ref "U1") (pin "11") (pinfunction "IO27_11") (pintype "bidirectional"))
    )
    (net (code "74") (name "/IO32") (class "Default")
      (node (ref "32_33_25_26_27_14_12_GND_13") (pin "1") (pinfunction "1_1") (pintype "bidirectional"))
      (node (ref "U$4") (pin "1") (pinfunction "1_1") (pintype "bidirectional"))
      (node (ref "U1") (pin "7") (pinfunction "IO32_7") (pintype "bidirectional"))
    )
    (net (code "75") (name "/IO33") (class "Default")
      (node (ref "32_33_25_26_27_14_12_GND_13") (pin "2") (pinfunction "2_2") (pintype "bidirectional"))
      (node (ref "U$4") (pin "2") (pinfunction "2_2") (pintype "bidirectional"))
      (node (ref "U1") (pin "8") (pinfunction "IO33_8") (pintype "bidirectional"))
    )
    (net (code "76") (name "/IO34") (class "Default")
      (node (ref "R2_220Ω") (pin "1") (pinfunction "1_1") (pintype "passive"))
      (node (ref "U1") (pin "5") (pinfunction "IO34_5") (pintype "bidirectional"))
    )
    (net (code "77") (name "/IO35") (class "Default")
      (node (ref "R1_220Ω") (pin "1") (pinfunction "1_1") (pintype "passive"))
      (node (ref "U1") (pin "6") (pinfunction "IO35_6") (pintype "bidirectional"))
    )
    (net (code "78") (name "/PA0") (class "Default")
      (node (ref "U$2") (pin "P$36") (pinfunction "PA0_P$36") (pintype "bidirectional"))
      (node (ref "U$30") (pin "5") (pinfunction "5_5") (pintype "bidirectional"))
      (node (ref "VBAT_PC13_PC14_PC15_PA0_PA1") (pin "5") (pinfunction "5_5") (pintype "bidirectional"))
    )
    (net (code "79") (name "/PA1") (class "Default")
      (node (ref "U$2") (pin "P$35") (pinfunction "PA1_P$35") (pintype "bidirectional"))
      (node (ref "U$30") (pin "6") (pinfunction "6_6") (pintype "bidirectional"))
      (node (ref "VBAT_PC13_PC14_PC15_PA0_PA1") (pin "6") (pinfunction "6_6") (pintype "bidirectional"))
    )
    (net (code "80") (name "/PA2") (class "Default")
      (node (ref "GND_PA3_PA2") (pin "3") (pinfunction "3_3") (pintype "bidirectional"))
      (node (ref "U$2") (pin "P$34") (pinfunction "PA2_P$34") (pintype "bidirectional"))
    )
    (net (code "81") (name "/PA3") (class "Default")
      (node (ref "GND_PA3_PA2") (pin "2") (pinfunction "2_2") (pintype "bidirectional"))
      (node (ref "U$2") (pin "P$33") (pinfunction "PA3_P$33") (pintype "bidirectional"))
    )
    (net (code "82") (name "/PA4") (class "Default")
      (node (ref "5V_GND1") (pin "1") (pinfunction "1_1") (pintype "bidirectional"))
      (node (ref "PA4_PA5_PA6_PA7") (pin "1") (pinfunction "1_1") (pintype "bidirectional"))
      (node (ref "U$2") (pin "P$32") (pinfunction "PA4_P$32") (pintype "bidirectional"))
    )
    (net (code "83") (name "/PA5") (class "Default")
      (node (ref "5V_GND1") (pin "2") (pinfunction "2_2") (pintype "bidirectional"))
      (node (ref "PA4_PA5_PA6_PA7") (pin "2") (pinfunction "2_2") (pintype "bidirectional"))
      (node (ref "U$2") (pin "P$31") (pinfunction "PA5_P$31") (pintype "bidirectional"))
    )
    (net (code "84") (name "/PA6") (class "Default")
      (node (ref "5V_GND1") (pin "3") (pinfunction "3_3") (pintype "bidirectional"))
      (node (ref "PA4_PA5_PA6_PA7") (pin "3") (pinfunction "3_3") (pintype "bidirectional"))
      (node (ref "U$2") (pin "P$30") (pinfunction "PA6_P$30") (pintype "bidirectional"))
    )
    (net (code "85") (name "/PA7") (class "Default")
      (node (ref "5V_GND1") (pin "4") (pinfunction "4_4") (pintype "bidirectional"))
      (node (ref "PA4_PA5_PA6_PA7") (pin "4") (pinfunction "4_4") (pintype "bidirectional"))
      (node (ref "U$2") (pin "P$29") (pinfunction "PA7_P$29") (pintype "bidirectional"))
    )
    (net (code "86") (name "/PA8") (class "Default")
      (node (ref "PA9_PA8_GND_5V") (pin "3") (pinfunction "3_3") (pintype "bidirectional"))
      (node (ref "U$2") (pin "P$5") (pinfunction "PA8_P$5") (pintype "bidirectional"))
    )
    (net (code "87") (name "/PA9") (class "Default")
      (node (ref "PA9_PA8_GND_5V") (pin "4") (pinfunction "4_4") (pintype "bidirectional"))
      (node (ref "U$2") (pin "P$6") (pinfunction "PA9_P$6") (pintype "bidirectional"))
    )
    (net (code "88") (name "/PA10") (class "Default")
      (node (ref "PA10_PA11_GND_5V") (pin "4") (pinfunction "4_4") (pintype "bidirectional"))
      (node (ref "U$2") (pin "P$7") (pinfunction "PA10_P$7") (pintype "bidirectional"))
    )
    (net (code "89") (name "/PA11") (class "Default")
      (node (ref "PA10_PA11_GND_5V") (pin "3") (pinfunction "3_3") (pintype "bidirectional"))
      (node (ref "U$2") (pin "P$8") (pinfunction "PA11_P$8") (pintype "bidirectional"))
    )
    (net (code "90") (name "/PA12") (class "Default")
      (node (ref "PA12_PA15_GND_5V") (pin "4") (pinfunction "4_4") (pintype "bidirectional"))
      (node (ref "U$2") (pin "P$9") (pinfunction "PA12_P$9") (pintype "bidirectional"))
    )
    (net (code "91") (name "/PA15") (class "Default")
      (node (ref "PA12_PA15_GND_5V") (pin "3") (pinfunction "3_3") (pintype "bidirectional"))
      (node (ref "U$2") (pin "P$10") (pinfunction "PA15_P$10") (pintype "bidirectional"))
    )
    (net (code "92") (name "/PB0") (class "Default")
      (node (ref "5V_GND_PB1_PB0") (pin "4") (pinfunction "4_4") (pintype "bidirectional"))
      (node (ref "U$2") (pin "P$28") (pinfunction "PB0_P$28") (pintype "bidirectional"))
    )
    (net (code "93") (name "/PB1") (class "Default")
      (node (ref "5V_GND_PB1_PB0") (pin "3") (pinfunction "3_3") (pintype "bidirectional"))
      (node (ref "U$2") (pin "P$27") (pinfunction "PB1_P$27") (pintype "bidirectional"))
    )
    (net (code "94") (name "/PB3") (class "Default")
      (node (ref "PB3_PB4_PB5_PB6_PB7_PB8_PB9") (pin "7") (pinfunction "7_7") (pintype "bidirectional"))
      (node (ref "U$2") (pin "P$11") (pinfunction "PB3_P$11") (pintype "bidirectional"))
      (node (ref "U$33") (pin "7") (pinfunction "7_7") (pintype "bidirectional"))
    )
    (net (code "95") (name "/PB4") (class "Default")
      (node (ref "PB3_PB4_PB5_PB6_PB7_PB8_PB9") (pin "6") (pinfunction "6_6") (pintype "bidirectional"))
      (node (ref "U$2") (pin "P$12") (pinfunction "PB4_P$12") (pintype "bidirectional"))
      (node (ref "U$33") (pin "6") (pinfunction "6_6") (pintype "bidirectional"))
    )
    (net (code "96") (name "/PB5") (class "Default")
      (node (ref "PB3_PB4_PB5_PB6_PB7_PB8_PB9") (pin "5") (pinfunction "5_5") (pintype "bidirectional"))
      (node (ref "U$2") (pin "P$13") (pinfunction "PB5_P$13") (pintype "bidirectional"))
      (node (ref "U$33") (pin "5") (pinfunction "5_5") (pintype "bidirectional"))
    )
    (net (code "97") (name "/PB6") (class "Default")
      (node (ref "PB3_PB4_PB5_PB6_PB7_PB8_PB9") (pin "4") (pinfunction "4_4") (pintype "bidirectional"))
      (node (ref "U$2") (pin "P$14") (pinfunction "PB6_P$14") (pintype "bidirectional"))
      (node (ref "U$33") (pin "4") (pinfunction "4_4") (pintype "bidirectional"))
    )
    (net (code "98") (name "/PB7") (class "Default")
      (node (ref "PB3_PB4_PB5_PB6_PB7_PB8_PB9") (pin "3") (pinfunction "3_3") (pintype "bidirectional"))
      (node (ref "U$2") (pin "P$15") (pinfunction "PB7_P$15") (pintype "bidirectional"))
      (node (ref "U$33") (pin "3") (pinfunction "3_3") (pintype "bidirectional"))
    )
    (net (code "99") (name "/PB8") (class "Default")
      (node (ref "PB3_PB4_PB5_PB6_PB7_PB8_PB9") (pin "2") (pinfunction "2_2") (pintype "bidirectional"))
      (node (ref "U$2") (pin "P$16") (pinfunction "PB8_P$16") (pintype "bidirectional"))
      (node (ref "U$33") (pin "2") (pinfunction "2_2") (pintype "bidirectional"))
    )
    (net (code "100") (name "/PB9") (class "Default")
      (node (ref "PB3_PB4_PB5_PB6_PB7_PB8_PB9") (pin "1") (pinfunction "1_1") (pintype "bidirectional"))
      (node (ref "U$2") (pin "P$17") (pinfunction "PB9_P$17") (pintype "bidirectional"))
      (node (ref "U$33") (pin "1") (pinfunction "1_1") (pintype "bidirectional"))
    )
    (net (code "101") (name "/PB10") (class "Default")
      (node (ref "PB10_PB11_RST_3V3_GND") (pin "1") (pinfunction "1_1") (pintype "bidirectional"))
      (node (ref "U$2") (pin "P$26") (pinfunction "PB10_P$26") (pintype "bidirectional"))
      (node (ref "U$26") (pin "1") (pinfunction "1_1") (pintype "bidirectional"))
    )
    (net (code "102") (name "/PB11") (class "Default")
      (node (ref "PB10_PB11_RST_3V3_GND") (pin "2") (pinfunction "2_2") (pintype "bidirectional"))
      (node (ref "U$2") (pin "P$25") (pinfunction "PB11_P$25") (pintype "bidirectional"))
      (node (ref "U$26") (pin "2") (pinfunction "2_2") (pintype "bidirectional"))
    )
    (net (code "103") (name "/PB12") (class "Default")
      (node (ref "PB12_PB13_PB14_PB15") (pin "4") (pinfunction "4_4") (pintype "bidirectional"))
      (node (ref "U$2") (pin "P$1") (pinfunction "PB12_P$1") (pintype "bidirectional"))
      (node (ref "U$35") (pin "4") (pinfunction "4_4") (pintype "bidirectional"))
    )
    (net (code "104") (name "/PB13") (class "Default")
      (node (ref "PB12_PB13_PB14_PB15") (pin "3") (pinfunction "3_3") (pintype "bidirectional"))
      (node (ref "U$2") (pin "P$2") (pinfunction "PB13_P$2") (pintype "bidirectional"))
      (node (ref "U$35") (pin "3") (pinfunction "3_3") (pintype "bidirectional"))
    )
    (net (code "105") (name "/PB14") (class "Default")
      (node (ref "PB12_PB13_PB14_PB15") (pin "2") (pinfunction "2_2") (pintype "bidirectional"))
      (node (ref "U$2") (pin "P$3") (pinfunction "PB14_P$3") (pintype "bidirectional"))
      (node (ref "U$35") (pin "2") (pinfunction "2_2") (pintype "bidirectional"))
    )
    (net (code "106") (name "/PB15") (class "Default")
      (node (ref "PB12_PB13_PB14_PB15") (pin "1") (pinfunction "1_1") (pintype "bidirectional"))
      (node (ref "U$2") (pin "P$4") (pinfunction "PB15_P$4") (pintype "bidirectional"))
      (node (ref "U$35") (pin "1") (pinfunction "1_1") (pintype "bidirectional"))
    )
    (net (code "107") (name "/PC13") (class "Default")
      (node (ref "U$2") (pin "P$39") (pinfunction "PC13_P$39") (pintype "bidirectional"))
      (node (ref "U$30") (pin "2") (pinfunction "2_2") (pintype "bidirectional"))
      (node (ref "VBAT_PC13_PC14_PC15_PA0_PA1") (pin "2") (pinfunction "2_2") (pintype "bidirectional"))
    )
    (net (code "108") (name "/PC14") (class "Default")
      (node (ref "U$2") (pin "P$38") (pinfunction "PC14_P$38") (pintype "bidirectional"))
      (node (ref "U$30") (pin "3") (pinfunction "3_3") (pintype "bidirectional"))
      (node (ref "VBAT_PC13_PC14_PC15_PA0_PA1") (pin "3") (pinfunction "3_3") (pintype "bidirectional"))
    )
    (net (code "109") (name "/PC15") (class "Default")
      (node (ref "U$2") (pin "P$37") (pinfunction "PC15_P$37") (pintype "bidirectional"))
      (node (ref "U$30") (pin "4") (pinfunction "4_4") (pintype "bidirectional"))
      (node (ref "VBAT_PC13_PC14_PC15_PA0_PA1") (pin "4") (pinfunction "4_4") (pintype "bidirectional"))
    )
    (net (code "110") (name "/RST") (class "Default")
      (node (ref "RST_3V3_GND") (pin "1") (pinfunction "1_1") (pintype "bidirectional"))
      (node (ref "U$1") (pin "P$24") (pinfunction "RESET_P$24") (pintype "bidirectional"))
      (node (ref "U$24") (pin "1") (pinfunction "1_1") (pintype "bidirectional"))
    )
    (net (code "111") (name "/RST1") (class "Default")
      (node (ref "PB10_PB11_RST_3V3_GND") (pin "3") (pinfunction "3_3") (pintype "bidirectional"))
      (node (ref "U$2") (pin "P$24") (pinfunction "RESET_P$24") (pintype "bidirectional"))
      (node (ref "U$26") (pin "3") (pinfunction "3_3") (pintype "bidirectional"))
    )
    (net (code "112") (name "/RX") (class "Default")
      (node (ref "TX_RX_GND") (pin "2") (pinfunction "2_2") (pintype "bidirectional"))
      (node (ref "U1") (pin "34") (pinfunction "RXD0_34") (pintype "input"))
    )
    (net (code "113") (name "/TX") (class "Default")
      (node (ref "TX_RX_GND") (pin "3") (pinfunction "3_3") (pintype "bidirectional"))
      (node (ref "U1") (pin "35") (pinfunction "TXD0_35") (pintype "output"))
    )
    (net (code "114") (name "/VBAT") (class "Default")
      (node (ref "U$1") (pin "P$40") (pinfunction "VBAT_P$40") (pintype "bidirectional"))
      (node (ref "U$18") (pin "1") (pinfunction "1_1") (pintype "bidirectional"))
      (node (ref "VBAT_C13_C14_C15") (pin "1") (pinfunction "1_1") (pintype "bidirectional"))
    )
    (net (code "115") (name "/VBAT1") (class "Default")
      (node (ref "U$2") (pin "P$40") (pinfunction "VBAT_P$40") (pintype "bidirectional"))
      (node (ref "U$30") (pin "1") (pinfunction "1_1") (pintype "bidirectional"))
      (node (ref "VBAT_PC13_PC14_PC15_PA0_PA1") (pin "1") (pinfunction "1_1") (pintype "bidirectional"))
    )
    (net (code "116") (name "/VN") (class "Default")
      (node (ref "3V3_EN_VP_VN") (pin "4") (pinfunction "4_4") (pintype "passive"))
      (node (ref "JP2") (pin "4") (pinfunction "4_4") (pintype "passive"))
      (node (ref "U1") (pin "4") (pinfunction "SENSOR_VN_4") (pintype "input"))
    )
    (net (code "117") (name "/VP") (class "Default")
      (node (ref "3V3_EN_VP_VN") (pin "3") (pinfunction "3_3") (pintype "passive"))
      (node (ref "JP2") (pin "3") (pinfunction "3_3") (pintype "passive"))
      (node (ref "U1") (pin "3") (pinfunction "SENSOR_VP_3") (pintype "input"))
    )
    (net (code "118") (name "GND") (class "Default")
      (node (ref "17_16_GND") (pin "1") (pinfunction "1_1") (pintype "bidirectional"))
      (node (ref "5V_GND") (pin "1") (pinfunction "1_1") (pintype "bidirectional"))
      (node (ref "GND_D2_D3") (pin "1") (pinfunction "1_1") (pintype "bidirectional"))
      (node (ref "GND_VCC") (pin "C") (pinfunction "C_C") (pintype "passive"))
      (node (ref "GND_VCC1") (pin "C") (pinfunction "C_C") (pintype "passive"))
      (node (ref "TX_RX_GND") (pin "1") (pinfunction "1_1") (pintype "bidirectional"))
      (node (ref "U1") (pin "38") (pinfunction "GND3_38") (pintype "power_in"))
    )
    (net (code "119") (name "Net-(5V_5V-Pad1)") (class "Default")
      (node (ref "5V_5V") (pin "1") (pinfunction "1_1") (pintype "passive"))
      (node (ref "D2") (pin "A") (pinfunction "A_A") (pintype "passive"))
    )
    (net (code "120") (name "Net-(5V_5V-Pad2)") (class "Default")
      (node (ref "5V_5V") (pin "2") (pinfunction "2_2") (pintype "passive"))
      (node (ref "5V_GND") (pin "2") (pinfunction "2_2") (pintype "bidirectional"))
    )
    (net (code "121") (name "Net-(5V_5V1-Pad1)") (class "Default")
      (node (ref "5V_5V1") (pin "1") (pinfunction "1_1") (pintype "passive"))
      (node (ref "D1") (pin "A") (pinfunction "A_A") (pintype "passive"))
    )
    (net (code "122") (name "Net-(5V_5V1-Pad2)") (class "Default")
      (node (ref "5V_5V1") (pin "2") (pinfunction "2_2") (pintype "passive"))
      (node (ref "GND_5V") (pin "2") (pinfunction "2_2") (pintype "bidirectional"))
    )
    (net (code "123") (name "Net-(5V_5V2-Pad1)") (class "Default")
      (node (ref "5V_5V2") (pin "1") (pinfunction "1_1") (pintype "passive"))
      (node (ref "D3") (pin "A") (pinfunction "A_A") (pintype "passive"))
    )
    (net (code "124") (name "Net-(5V_5V2-Pad2)") (class "Default")
      (node (ref "5V_5V2") (pin "2") (pinfunction "2_2") (pintype "passive"))
      (node (ref "J5") (pin "2") (pinfunction "2_2") (pintype "bidirectional"))
    )
    (net (code "125") (name "Net-(GND_VCC-PadA)") (class "Default")
      (node (ref "GND_VCC") (pin "A") (pinfunction "A_A") (pintype "passive"))
      (node (ref "R1_220Ω") (pin "2") (pinfunction "2_2") (pintype "passive"))
    )
    (net (code "126") (name "Net-(GND_VCC1-PadA)") (class "Default")
      (node (ref "GND_VCC1") (pin "A") (pinfunction "A_A") (pintype "passive"))
      (node (ref "R2_220Ω") (pin "2") (pinfunction "2_2") (pintype "passive"))
    )
    (net (code "127") (name "unconnected-(5V_5V-Pad3)") (class "Default")
      (node (ref "5V_5V") (pin "3") (pinfunction "3_3") (pintype "passive"))
    )
    (net (code "128") (name "unconnected-(5V_5V1-Pad3)") (class "Default")
      (node (ref "5V_5V1") (pin "3") (pinfunction "3_3") (pintype "passive"))
    )
    (net (code "129") (name "unconnected-(5V_5V2-Pad3)") (class "Default")
      (node (ref "5V_5V2") (pin "3") (pinfunction "3_3") (pintype "passive"))
    )
  )
)
